# 555.net
KiCad netlist of a schematic drawn in EAGLE
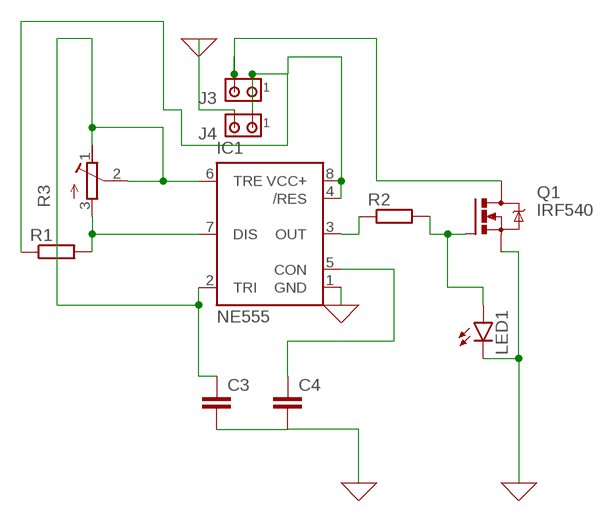
[diagram p0: schematic, sheet 1]

(export (version "E")
  (design (tool "Eeschema 10.0.6"))
  (components
    (comp (ref "C3")
      (value "C2.5/5")
      (footprint "eagle-import:C2.5-5")
      (libsource (lib "eagle-import") (part "C2.5/5"))
    )
    (comp (ref "C4")
      (value "C2.5/5")
      (footprint "eagle-import:C2.5-5")
      (libsource (lib "eagle-import") (part "C2.5/5"))
    )
    (comp (ref "IC1")
      (value "NE555")
      (footprint "eagle-import:DIL-08")
      (fields (field (name "MF") "Arrow Electronics") (field (name "MPN") "NE555N"))
      (libsource (lib "eagle-import") (part "NE555"))
    )
    (comp (ref "J3")
      (value "MTA02-100")
      (footprint "eagle-import:10X02MTA")
      (libsource (lib "eagle-import") (part "MTA02-100"))
    )
    (comp (ref "J4")
      (value "MTA02-100")
      (footprint "eagle-import:10X02MTA")
      (libsource (lib "eagle-import") (part "MTA02-100"))
    )
    (comp (ref "LED1")
      (value "LEDSQR2X5")
      (footprint "eagle-import:LED2X5")
      (libsource (lib "eagle-import") (part "LEDSQR2X5"))
    )
    (comp (ref "Q1")
      (value "IRF540")
      (footprint "eagle-import:TO220BV")
      (libsource (lib "eagle-import") (part "IRF540"))
    )
    (comp (ref "R1")
      (value "R-EU_0204/5")
      (footprint "eagle-import:0204_5")
      (libsource (lib "eagle-import") (part "R-EU_0204/5"))
    )
    (comp (ref "R2")
      (value "R-EU_0207/7")
      (footprint "eagle-import:0207_7")
      (libsource (lib "eagle-import") (part "R-EU_0207/7"))
    )
    (comp (ref "R3")
      (value "R-TRIMMT93XA")
      (footprint "eagle-import:RTRIMT93XA")
      (libsource (lib "eagle-import") (part "R-TRIMMT93XA"))
    )
  )
  (nets
    (net (code "1") (name "GND") (class "Default")
      (node (ref "C3") (pin "2") (pinfunction "2_2") (pintype "passive"))
      (node (ref "C4") (pin "2") (pinfunction "2_2") (pintype "passive"))
      (node (ref "IC1") (pin "1") (pinfunction "GND_1") (pintype "power_in"))
      (node (ref "J4") (pin "2") (pinfunction "2_2") (pintype "passive"))
      (node (ref "LED1") (pin "K") (pinfunction "C_K") (pintype "passive"))
      (node (ref "Q1") (pin "S") (pinfunction "S_S") (pintype "passive"))
    )
    (net (code "2") (name "Net-(IC1-CON)") (class "Default")
      (node (ref "C4") (pin "1") (pinfunction "1_1") (pintype "passive"))
      (node (ref "IC1") (pin "5") (pinfunction "CON_5") (pintype "input"))
    )
    (net (code "3") (name "Net-(IC1-DIS)") (class "Default")
      (node (ref "IC1") (pin "7") (pinfunction "DIS_7") (pintype "input"))
      (node (ref "R1") (pin "2") (pinfunction "2_2") (pintype "passive"))
      (node (ref "R3") (pin "3") (pinfunction "A_3") (pintype "passive"))
    )
    (net (code "4") (name "Net-(IC1-OUT)") (class "Default")
      (node (ref "IC1") (pin "3") (pinfunction "OUT_3") (pintype "output"))
      (node (ref "R2") (pin "1") (pinfunction "1_1") (pintype "passive"))
    )
    (net (code "5") (name "Net-(IC1-TRE)") (class "Default")
      (node (ref "C3") (pin "1") (pinfunction "1_1") (pintype "passive"))
      (node (ref "IC1") (pin "2") (pinfunction "TRI_2") (pintype "input"))
      (node (ref "IC1") (pin "6") (pinfunction "TRE_6") (pintype "input"))
      (node (ref "R3") (pin "1") (pinfunction "E_1") (pintype "passive"))
      (node (ref "R3") (pin "2") (pinfunction "S_2") (pintype "passive"))
    )
    (net (code "6") (name "Net-(IC1-VCC+)") (class "Default")
      (node (ref "IC1") (pin "4") (pinfunction "/RES_4") (pintype "input"))
      (node (ref "IC1") (pin "8") (pinfunction "VCC+_8") (pintype "power_in"))
      (node (ref "J3") (pin "1") (pinfunction "1_1") (pintype "passive"))
      (node (ref "J4") (pin "1") (pinfunction "1_1") (pintype "passive"))
      (node (ref "R1") (pin "1") (pinfunction "1_1") (pintype "passive"))
    )
    (net (code "7") (name "Net-(J3-Pad2)") (class "Default")
      (node (ref "J3") (pin "2") (pinfunction "2_2") (pintype "passive"))
      (node (ref "Q1") (pin "D") (pinfunction "D_D") (pintype "passive"))
    )
    (net (code "8") (name "Net-(LED1-PadA)") (class "Default")
      (node (ref "LED1") (pin "A") (pinfunction "A_A") (pintype "passive"))
      (node (ref "Q1") (pin "G") (pinfunction "G_G") (pintype "passive"))
      (node (ref "R2") (pin "2") (pinfunction "2_2") (pintype "passive"))
    )
  )
)
